# LNA.net
KiCad netlist of a schematic drawn in EAGLE
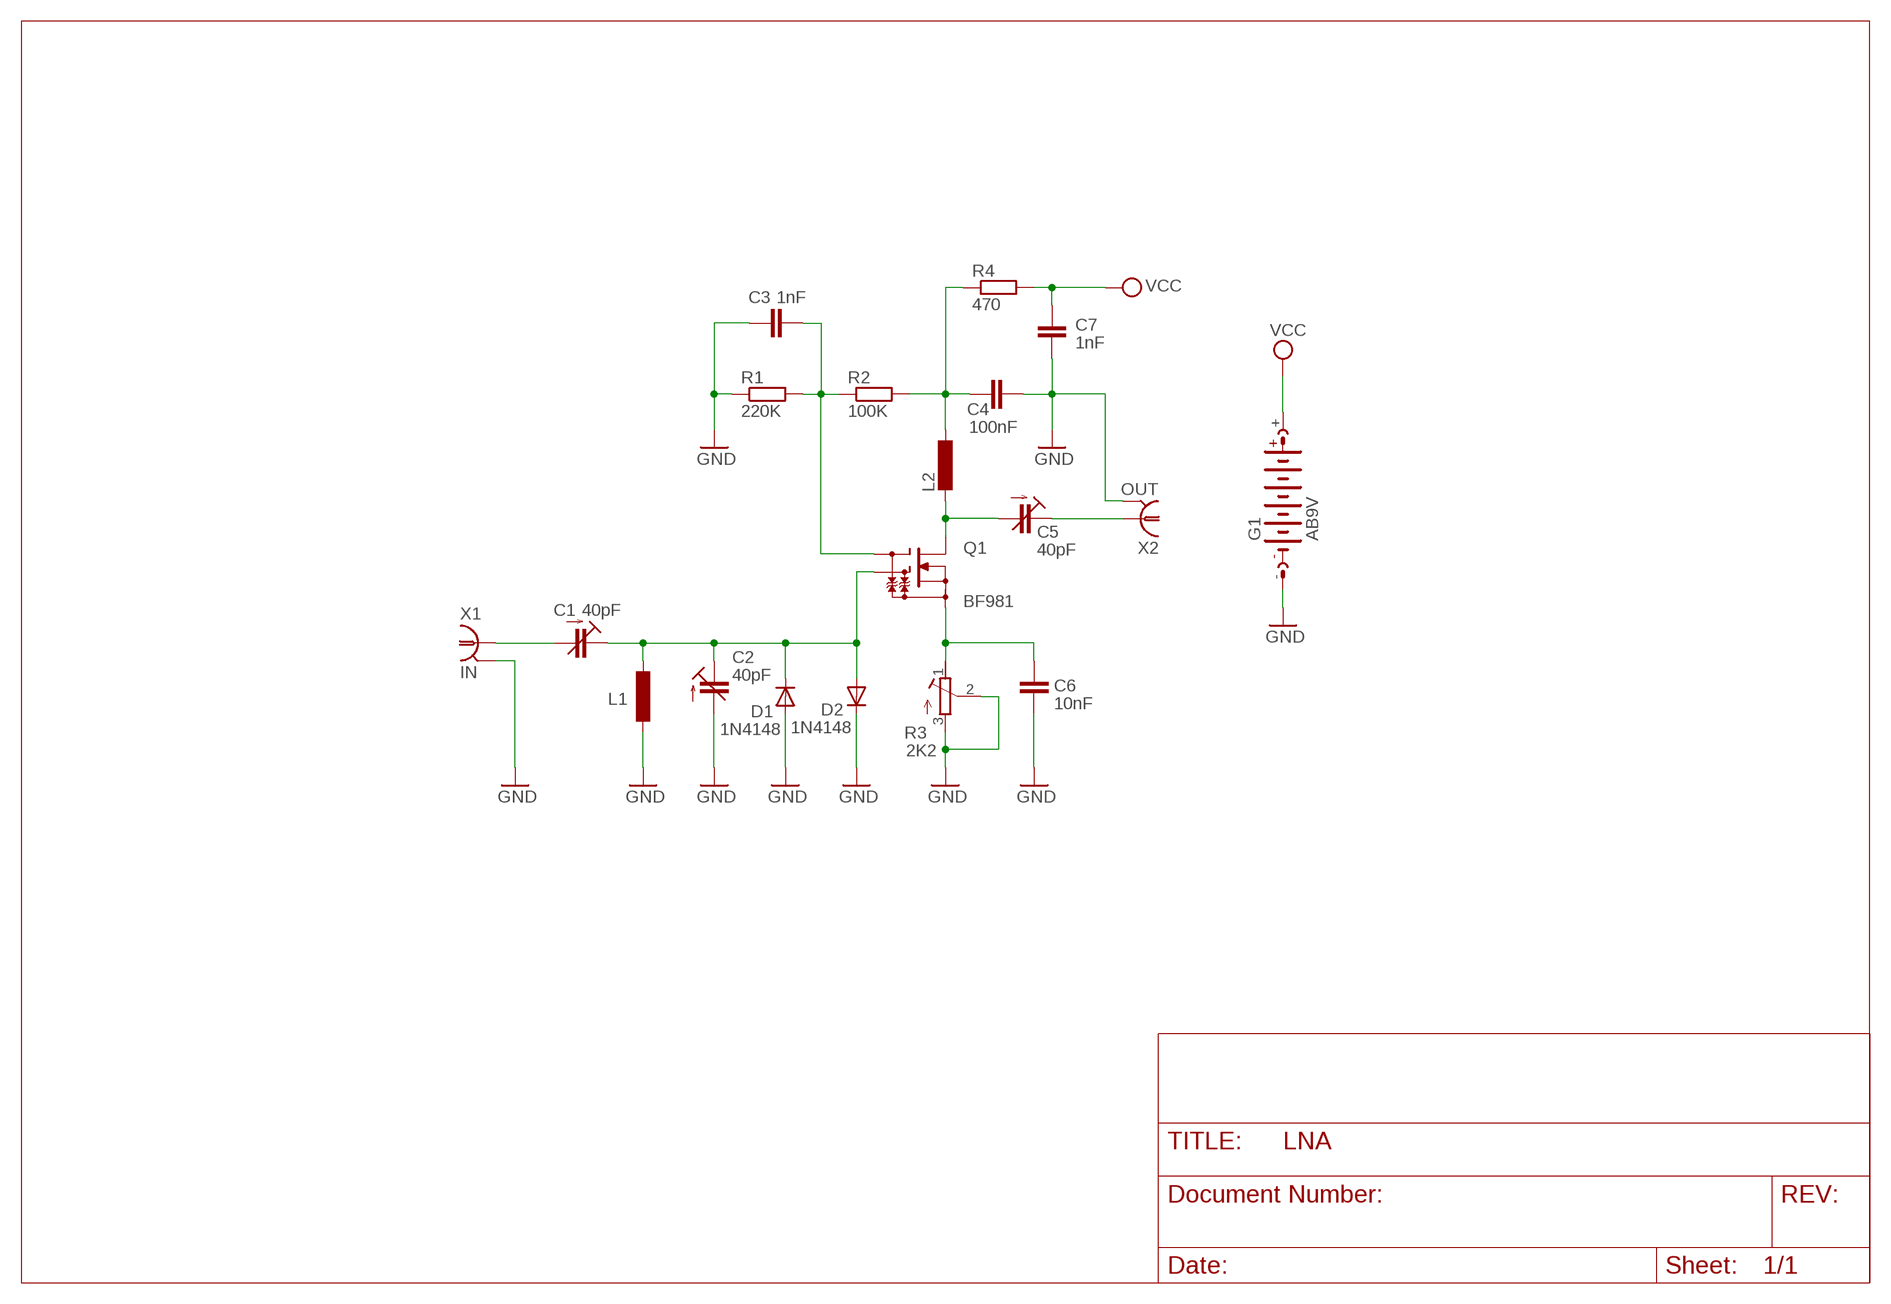
[diagram p0: schematic, sheet 1]

(export (version "E")
  (design (tool "Eeschema 10.0.6"))
  (components
    (comp (ref "C1")
      (value "40pF")
      (footprint "eagle-import:CTRIM808-BC")
      (libsource (lib "eagle-import") (part "C-TRIMM808"))
    )
    (comp (ref "C2")
      (value "40pF")
      (footprint "eagle-import:CTRIM808-BC")
      (libsource (lib "eagle-import") (part "C-TRIMM808"))
    )
    (comp (ref "C3")
      (value "1nF")
      (footprint "eagle-import:C050-025X075")
      (libsource (lib "eagle-import") (part "C-EU050-025X075"))
    )
    (comp (ref "C4")
      (value "100nF")
      (footprint "eagle-import:C050-025X075")
      (libsource (lib "eagle-import") (part "C-EU050-025X075"))
    )
    (comp (ref "C5")
      (value "40pF")
      (footprint "eagle-import:CTRIM808-BC")
      (libsource (lib "eagle-import") (part "C-TRIMM808"))
    )
    (comp (ref "C6")
      (value "10nF")
      (footprint "eagle-import:C050-025X075")
      (libsource (lib "eagle-import") (part "C-EU050-025X075"))
    )
    (comp (ref "C7")
      (value "1nF")
      (footprint "eagle-import:C050-025X075")
      (libsource (lib "eagle-import") (part "C-EU050-025X075"))
    )
    (comp (ref "D1")
      (value "1N4148")
      (footprint "eagle-import:DO35-7")
      (libsource (lib "eagle-import") (part "1N4148DO35-7"))
    )
    (comp (ref "D2")
      (value "1N4148")
      (footprint "eagle-import:DO35-7")
      (libsource (lib "eagle-import") (part "1N4148DO35-7"))
    )
    (comp (ref "G1")
      (value "AB9V")
      (footprint "eagle-import:AB9V")
      (libsource (lib "eagle-import") (part "AB9V"))
    )
    (comp (ref "L1")
      (value "L-EU0204/5")
      (footprint "eagle-import:0204_5")
      (libsource (lib "eagle-import") (part "L-EU0204/5"))
    )
    (comp (ref "L2")
      (value "L-EU0204/5")
      (footprint "eagle-import:0204_5")
      (libsource (lib "eagle-import") (part "L-EU0204/5"))
    )
    (comp (ref "Q1")
      (value "BF981")
      (footprint "eagle-import:SOT103")
      (libsource (lib "eagle-import") (part "BF981"))
    )
    (comp (ref "R1")
      (value "220K")
      (footprint "eagle-import:0207_10")
      (libsource (lib "eagle-import") (part "R-EU_0207/10"))
    )
    (comp (ref "R2")
      (value "100K")
      (footprint "eagle-import:0207_10")
      (libsource (lib "eagle-import") (part "R-EU_0207/10"))
    )
    (comp (ref "R3")
      (value "2K2")
      (footprint "eagle-import:RTRIM43P")
      (libsource (lib "eagle-import") (part "R-TRIMM43P"))
    )
    (comp (ref "R4")
      (value "470")
      (footprint "eagle-import:0207_10")
      (libsource (lib "eagle-import") (part "R-EU_0207/10"))
    )
    (comp (ref "X1")
      (value "IN")
      (footprint "eagle-import:A1944")
      (libsource (lib "eagle-import") (part "A1944-50"))
    )
    (comp (ref "X2")
      (value "OUT")
      (footprint "eagle-import:A1944")
      (libsource (lib "eagle-import") (part "A1944-50"))
    )
  )
  (nets
    (net (code "1") (name "GND") (class "Default")
      (node (ref "C2") (pin "2") (pinfunction "A_2") (pintype "passive"))
      (node (ref "C3") (pin "1") (pinfunction "1_1") (pintype "passive"))
      (node (ref "C4") (pin "2") (pinfunction "2_2") (pintype "passive"))
      (node (ref "C6") (pin "2") (pinfunction "2_2") (pintype "passive"))
      (node (ref "C7") (pin "2") (pinfunction "2_2") (pintype "passive"))
      (node (ref "D1") (pin "A") (pinfunction "A_A") (pintype "passive"))
      (node (ref "D2") (pin "C") (pinfunction "C_C") (pintype "passive"))
      (node (ref "G1") (pin "-") (pinfunction "-_-") (pintype "passive"))
      (node (ref "L1") (pin "2") (pinfunction "2_2") (pintype "passive"))
      (node (ref "R1") (pin "1") (pinfunction "1_1") (pintype "passive"))
      (node (ref "R3") (pin "2") (pinfunction "S_2") (pintype "passive"))
      (node (ref "R3") (pin "3") (pinfunction "E_3") (pintype "passive"))
      (node (ref "X1") (pin "2") (pinfunction "2_2") (pintype "passive"))
      (node (ref "X1") (pin "3") (pinfunction "2_3") (pintype "passive"))
      (node (ref "X1") (pin "4") (pinfunction "2_4") (pintype "passive"))
      (node (ref "X1") (pin "5") (pinfunction "2_5") (pintype "passive"))
      (node (ref "X2") (pin "2") (pinfunction "2_2") (pintype "passive"))
      (node (ref "X2") (pin "3") (pinfunction "2_3") (pintype "passive"))
      (node (ref "X2") (pin "4") (pinfunction "2_4") (pintype "passive"))
      (node (ref "X2") (pin "5") (pinfunction "2_5") (pintype "passive"))
    )
    (net (code "2") (name "Net-(C1-A)") (class "Default")
      (node (ref "C1") (pin "2") (pinfunction "A_2") (pintype "passive"))
      (node (ref "X1") (pin "1") (pinfunction "1_1") (pintype "passive"))
    )
    (net (code "3") (name "Net-(C1-E)") (class "Default")
      (node (ref "C1") (pin "1") (pinfunction "E_1") (pintype "passive"))
      (node (ref "C2") (pin "1") (pinfunction "E_1") (pintype "passive"))
      (node (ref "D1") (pin "C") (pinfunction "C_C") (pintype "passive"))
      (node (ref "D2") (pin "A") (pinfunction "A_A") (pintype "passive"))
      (node (ref "L1") (pin "1") (pinfunction "1_1") (pintype "passive"))
      (node (ref "Q1") (pin "3-G2") (pinfunction "G2_3-G2") (pintype "passive"))
    )
    (net (code "4") (name "Net-(C4-Pad1)") (class "Default")
      (node (ref "C4") (pin "1") (pinfunction "1_1") (pintype "passive"))
      (node (ref "L2") (pin "1") (pinfunction "1_1") (pintype "passive"))
      (node (ref "R2") (pin "2") (pinfunction "2_2") (pintype "passive"))
      (node (ref "R4") (pin "1") (pinfunction "1_1") (pintype "passive"))
    )
    (net (code "5") (name "Net-(C5-A)") (class "Default")
      (node (ref "C5") (pin "2") (pinfunction "A_2") (pintype "passive"))
      (node (ref "L2") (pin "2") (pinfunction "2_2") (pintype "passive"))
      (node (ref "Q1") (pin "2-D") (pinfunction "DRAIN_2-D") (pintype "passive"))
    )
    (net (code "6") (name "Net-(C5-E)") (class "Default")
      (node (ref "C5") (pin "1") (pinfunction "E_1") (pintype "passive"))
      (node (ref "X2") (pin "1") (pinfunction "1_1") (pintype "passive"))
    )
    (net (code "7") (name "Net-(Q1-G1)") (class "Default")
      (node (ref "C3") (pin "2") (pinfunction "2_2") (pintype "passive"))
      (node (ref "Q1") (pin "4-G1") (pinfunction "G1_4-G1") (pintype "passive"))
      (node (ref "R1") (pin "2") (pinfunction "2_2") (pintype "passive"))
      (node (ref "R2") (pin "1") (pinfunction "1_1") (pintype "passive"))
    )
    (net (code "8") (name "Net-(Q1-SOURCE)") (class "Default")
      (node (ref "C6") (pin "1") (pinfunction "1_1") (pintype "passive"))
      (node (ref "Q1") (pin "1-S") (pinfunction "SOURCE_1-S") (pintype "passive"))
      (node (ref "R3") (pin "1") (pinfunction "A_1") (pintype "passive"))
    )
    (net (code "9") (name "VCC") (class "Default")
      (node (ref "C7") (pin "1") (pinfunction "1_1") (pintype "passive"))
      (node (ref "G1") (pin "+") (pinfunction "+_+") (pintype "passive"))
      (node (ref "R4") (pin "2") (pinfunction "2_2") (pintype "passive"))
    )
  )
)
